# Schematic.net
KiCad netlist of a schematic drawn in Altium Designer
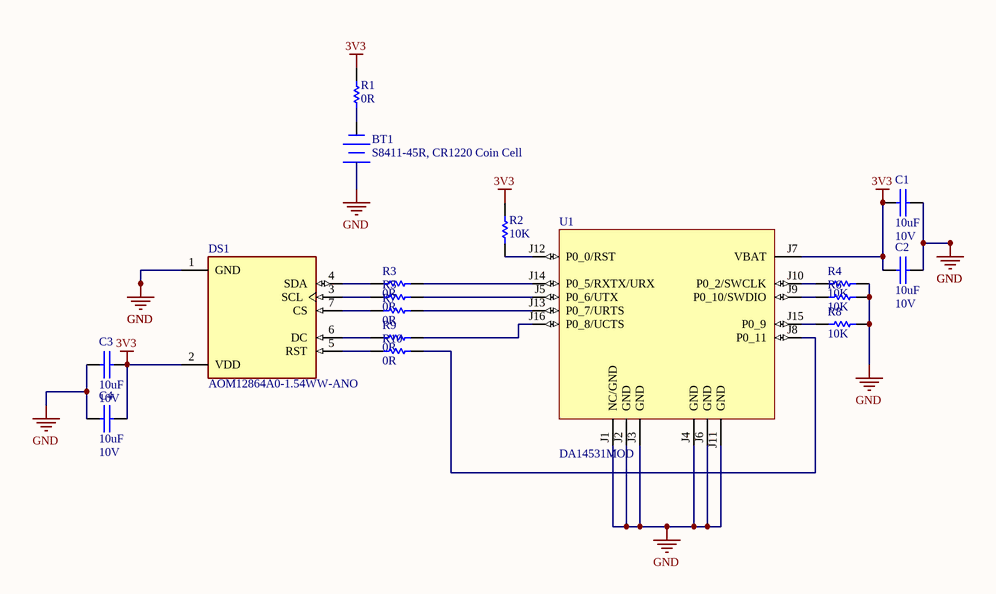
[diagram p0: Schematic.SchDoc]

(export (version "E")
  (design (tool "Eeschema 10.0.6"))
  (components
    (comp (ref "BT1")
      (value "S8411-45R, CR1220 Coin Cell")
      (footprint "HWN_S8411-45R")
      (description "Battery Holder, 12 mm Coin Cell, CR1220 SM")
      (fields (field (name "MANUFACTURER'S PART #") "S8411-45R") (field (name "MANUFACTURER") "Harwin"))
      (libsource (lib "Low Power Bluetooth PMOD RevA") (part "BT-S8411-45R-SR-HWN"))
    )
    (comp (ref "C1")
      (value "10uF")
      (footprint "CAPC1608X10N")
      (description "Capacitor, 10uF, 10V, SM")
      (fields
        (field (name "MANUFACTURER'S PART #") "GRM188R61A106KE69D")
        (field (name "MANUFACTURER") "Murata")
        (field (name "VOLTAGE RATING") "10V")
      )
      (libsource (lib "Low Power Bluetooth PMOD RevA") (part "CI-10uF-10V-X5R-SR-MRT"))
    )
    (comp (ref "C2")
      (value "10uF")
      (footprint "CAPC1608X10N")
      (description "Capacitor, 10uF, 10V, SM")
      (fields
        (field (name "MANUFACTURER'S PART #") "GRM188R61A106KE69D")
        (field (name "MANUFACTURER") "Murata")
        (field (name "VOLTAGE RATING") "10V")
      )
      (libsource (lib "Low Power Bluetooth PMOD RevA") (part "CI-10uF-10V-X5R-SR-MRT"))
    )
    (comp (ref "C3")
      (value "10uF")
      (footprint "CAPC1608X10N")
      (description "Capacitor, 10uF, 10V, SM")
      (fields
        (field (name "MANUFACTURER'S PART #") "GRM188R61A106KE69D")
        (field (name "MANUFACTURER") "Murata")
        (field (name "VOLTAGE RATING") "10V")
      )
      (libsource (lib "Low Power Bluetooth PMOD RevA") (part "CI-10uF-10V-X5R-SR-MRT"))
    )
    (comp (ref "C4")
      (value "10uF")
      (footprint "CAPC1608X10N")
      (description "Capacitor, 10uF, 10V, SM")
      (fields
        (field (name "MANUFACTURER'S PART #") "GRM188R61A106KE69D")
        (field (name "MANUFACTURER") "Murata")
        (field (name "VOLTAGE RATING") "10V")
      )
      (libsource (lib "Low Power Bluetooth PMOD RevA") (part "CI-10uF-10V-X5R-SR-MRT"))
    )
    (comp (ref "DS1")
      (value "AOM12864A0-1.54WW-ANO")
      (footprint "LCD_AOM12864A0-1.54WW-ANO")
      (description "Non-Touch Graphic LCD Display Module - White OLED SPI 1.54 (39.12mm) 128 x 64")
      (fields (field (name "MF") "Orient Display"))
      (libsource (lib "AOM12864A0-1.54WW-ANO") (part "AOM12864A0-1.54WW-ANO"))
    )
    (comp (ref "R1")
      (value "0R")
      (footprint "RESC1608X06N")
      (description "Resistor, 0 ohms, 1/8W, 1%, SM")
      (fields (field (name "MANUFACTURER'S PART #") "RK73Z1JTTD") (field (name "MANUFACTURER") "KOA Speer"))
      (libsource (lib "Low Power Bluetooth PMOD RevA") (part "RP-0-SR-KOA"))
    )
    (comp (ref "R2")
      (value "10K")
      (footprint "RESC1608X06N")
      (description "Resistor, 10K ohms, 1/8W, 1%, SM")
      (fields
        (field (name "MANUFACTURER'S PART #") "RK73H1JTTD1002F")
        (field (name "MANUFACTURER") "KOA Speer")
      )
      (libsource (lib "Low Power Bluetooth PMOD RevA") (part "RP-10K-SR-KOA"))
    )
    (comp (ref "R3")
      (value "0R")
      (footprint "RESC1608X06N")
      (description "Resistor, 0 ohms, 1/8W, 1%, SM")
      (fields (field (name "MANUFACTURER'S PART #") "RK73Z1JTTD") (field (name "MANUFACTURER") "KOA Speer"))
      (libsource (lib "Low Power Bluetooth PMOD RevA") (part "RP-0-SR-KOA"))
    )
    (comp (ref "R4")
      (value "10K")
      (footprint "RESC1608X06N")
      (description "Resistor, 10K ohms, 1/8W, 1%, SM")
      (fields
        (field (name "MANUFACTURER'S PART #") "RK73H1JTTD1002F")
        (field (name "MANUFACTURER") "KOA Speer")
      )
      (libsource (lib "Low Power Bluetooth PMOD RevA") (part "RP-10K-SR-KOA"))
    )
    (comp (ref "R5")
      (value "0R")
      (footprint "RESC1608X06N")
      (description "Resistor, 0 ohms, 1/8W, 1%, SM")
      (fields (field (name "MANUFACTURER'S PART #") "RK73Z1JTTD") (field (name "MANUFACTURER") "KOA Speer"))
      (libsource (lib "Low Power Bluetooth PMOD RevA") (part "RP-0-SR-KOA"))
    )
    (comp (ref "R6")
      (value "10K")
      (footprint "RESC1608X06N")
      (description "Resistor, 10K ohms, 1/8W, 1%, SM")
      (fields
        (field (name "MANUFACTURER'S PART #") "RK73H1JTTD1002F")
        (field (name "MANUFACTURER") "KOA Speer")
      )
      (libsource (lib "Low Power Bluetooth PMOD RevA") (part "RP-10K-SR-KOA"))
    )
    (comp (ref "R7")
      (value "0R")
      (footprint "RESC1608X06N")
      (description "Resistor, 0 ohms, 1/8W, 1%, SM")
      (fields (field (name "MANUFACTURER'S PART #") "RK73Z1JTTD") (field (name "MANUFACTURER") "KOA Speer"))
      (libsource (lib "Low Power Bluetooth PMOD RevA") (part "RP-0-SR-KOA"))
    )
    (comp (ref "R8")
      (value "10K")
      (footprint "RESC1608X06N")
      (description "Resistor, 10K ohms, 1/8W, 1%, SM")
      (fields
        (field (name "MANUFACTURER'S PART #") "RK73H1JTTD1002F")
        (field (name "MANUFACTURER") "KOA Speer")
      )
      (libsource (lib "Low Power Bluetooth PMOD RevA") (part "RP-10K-SR-KOA"))
    )
    (comp (ref "R9")
      (value "0R")
      (footprint "RESC1608X06N")
      (description "Resistor, 0 ohms, 1/8W, 1%, SM")
      (fields (field (name "MANUFACTURER'S PART #") "RK73Z1JTTD") (field (name "MANUFACTURER") "KOA Speer"))
      (libsource (lib "Low Power Bluetooth PMOD RevA") (part "RP-0-SR-KOA"))
    )
    (comp (ref "R10")
      (value "0R")
      (footprint "RESC1608X06N")
      (description "Resistor, 0 ohms, 1/8W, 1%, SM")
      (fields (field (name "MANUFACTURER'S PART #") "RK73Z1JTTD") (field (name "MANUFACTURER") "KOA Speer"))
      (libsource (lib "Low Power Bluetooth PMOD RevA") (part "RP-0-SR-KOA"))
    )
    (comp (ref "U1")
      (value "DA14531MOD")
      (footprint "DLG_DA14531MOD-00F01002")
      (description "DA14531MOD, Bluetooth Low Energy 5.1 Module, SM")
      (libsource (lib "Low Power Bluetooth PMOD RevA") (part "UD-DA14531MOD-00F01002-SR-DLG"))
    )
  )
  (nets
    (net (code "1") (name "3V3") (class "Default")
      (node (ref "C1") (pin "1") (pinfunction "1_1") (pintype "passive"))
      (node (ref "C2") (pin "1") (pinfunction "1_1") (pintype "passive"))
      (node (ref "C3") (pin "2") (pinfunction "2_2") (pintype "passive"))
      (node (ref "C4") (pin "2") (pinfunction "2_2") (pintype "passive"))
      (node (ref "DS1") (pin "2") (pinfunction "VDD_2") (pintype "power_in"))
      (node (ref "R1") (pin "1") (pinfunction "1_1") (pintype "passive"))
      (node (ref "R2") (pin "1") (pinfunction "1_1") (pintype "passive"))
      (node (ref "U1") (pin "J7") (pinfunction "VBAT_J7") (pintype "power_in"))
    )
    (net (code "2") (name "GND") (class "Default")
      (node (ref "BT1") (pin "1") (pinfunction "+_1") (pintype "passive"))
      (node (ref "C1") (pin "2") (pinfunction "2_2") (pintype "passive"))
      (node (ref "C2") (pin "2") (pinfunction "2_2") (pintype "passive"))
      (node (ref "C3") (pin "1") (pinfunction "1_1") (pintype "passive"))
      (node (ref "C4") (pin "1") (pinfunction "1_1") (pintype "passive"))
      (node (ref "DS1") (pin "1") (pinfunction "GND_1") (pintype "power_in"))
      (node (ref "R4") (pin "2") (pinfunction "2_2") (pintype "passive"))
      (node (ref "R6") (pin "2") (pinfunction "2_2") (pintype "passive"))
      (node (ref "R8") (pin "2") (pinfunction "2_2") (pintype "passive"))
      (node (ref "U1") (pin "J1") (pinfunction "NC/GND_J1") (pintype "power_in"))
      (node (ref "U1") (pin "J11") (pinfunction "GND_J11") (pintype "power_in"))
      (node (ref "U1") (pin "J2") (pinfunction "GND_J2") (pintype "power_in"))
      (node (ref "U1") (pin "J3") (pinfunction "GND_J3") (pintype "power_in"))
      (node (ref "U1") (pin "J4") (pinfunction "GND_J4") (pintype "power_in"))
      (node (ref "U1") (pin "J6") (pinfunction "GND_J6") (pintype "power_in"))
    )
    (net (code "3") (name "Net-(BT1--)") (class "Default")
      (node (ref "BT1") (pin "2") (pinfunction "-_2") (pintype "passive"))
      (node (ref "R1") (pin "2") (pinfunction "2_2") (pintype "passive"))
    )
    (net (code "4") (name "Net-(DS1-CS)") (class "Default")
      (node (ref "DS1") (pin "7") (pinfunction "CS_7") (pintype "input"))
      (node (ref "R7") (pin "1") (pinfunction "1_1") (pintype "passive"))
    )
    (net (code "5") (name "Net-(DS1-DC)") (class "Default")
      (node (ref "DS1") (pin "6") (pinfunction "DC_6") (pintype "input"))
      (node (ref "R9") (pin "1") (pinfunction "1_1") (pintype "passive"))
    )
    (net (code "6") (name "Net-(DS1-RST)") (class "Default")
      (node (ref "DS1") (pin "5") (pinfunction "RST_5") (pintype "input"))
      (node (ref "R10") (pin "1") (pinfunction "1_1") (pintype "passive"))
    )
    (net (code "7") (name "Net-(DS1-SCL)") (class "Default")
      (node (ref "DS1") (pin "3") (pinfunction "SCL_3") (pintype "input"))
      (node (ref "R5") (pin "1") (pinfunction "1_1") (pintype "passive"))
    )
    (net (code "8") (name "Net-(DS1-SDA)") (class "Default")
      (node (ref "DS1") (pin "4") (pinfunction "SDA_4") (pintype "bidirectional"))
      (node (ref "R3") (pin "1") (pinfunction "1_1") (pintype "passive"))
    )
    (net (code "9") (name "Net-(U1-P0_0{slash}RST)") (class "Default")
      (node (ref "R2") (pin "2") (pinfunction "2_2") (pintype "passive"))
      (node (ref "U1") (pin "J12") (pinfunction "P0_0/RST_J12") (pintype "bidirectional"))
    )
    (net (code "10") (name "Net-(U1-P0_2{slash}SWCLK)") (class "Default")
      (node (ref "R4") (pin "1") (pinfunction "1_1") (pintype "passive"))
      (node (ref "U1") (pin "J10") (pinfunction "P0_2/SWCLK_J10") (pintype "bidirectional"))
    )
    (net (code "11") (name "Net-(U1-P0_5{slash}RXTX{slash}URX)") (class "Default")
      (node (ref "R3") (pin "2") (pinfunction "2_2") (pintype "passive"))
      (node (ref "U1") (pin "J14") (pinfunction "P0_5/RXTX/URX_J14") (pintype "bidirectional"))
    )
    (net (code "12") (name "Net-(U1-P0_6{slash}UTX)") (class "Default")
      (node (ref "R5") (pin "2") (pinfunction "2_2") (pintype "passive"))
      (node (ref "U1") (pin "J5") (pinfunction "P0_6/UTX_J5") (pintype "bidirectional"))
    )
    (net (code "13") (name "Net-(U1-P0_7{slash}URTS)") (class "Default")
      (node (ref "R7") (pin "2") (pinfunction "2_2") (pintype "passive"))
      (node (ref "U1") (pin "J13") (pinfunction "P0_7/URTS_J13") (pintype "bidirectional"))
    )
    (net (code "14") (name "Net-(U1-P0_8{slash}UCTS)") (class "Default")
      (node (ref "R9") (pin "2") (pinfunction "2_2") (pintype "passive"))
      (node (ref "U1") (pin "J16") (pinfunction "P0_8/UCTS_J16") (pintype "bidirectional"))
    )
    (net (code "15") (name "Net-(U1-P0_9)") (class "Default")
      (node (ref "R8") (pin "1") (pinfunction "1_1") (pintype "passive"))
      (node (ref "U1") (pin "J15") (pinfunction "P0_9_J15") (pintype "bidirectional"))
    )
    (net (code "16") (name "Net-(U1-P0_10{slash}SWDIO)") (class "Default")
      (node (ref "R6") (pin "1") (pinfunction "1_1") (pintype "passive"))
      (node (ref "U1") (pin "J9") (pinfunction "P0_10/SWDIO_J9") (pintype "bidirectional"))
    )
    (net (code "17") (name "Net-(U1-P0_11)") (class "Default")
      (node (ref "R10") (pin "2") (pinfunction "2_2") (pintype "passive"))
      (node (ref "U1") (pin "J8") (pinfunction "P0_11_J8") (pintype "bidirectional"))
    )
  )
)
